# Sheet1.net
KiCad netlist of a schematic drawn in Altium Designer
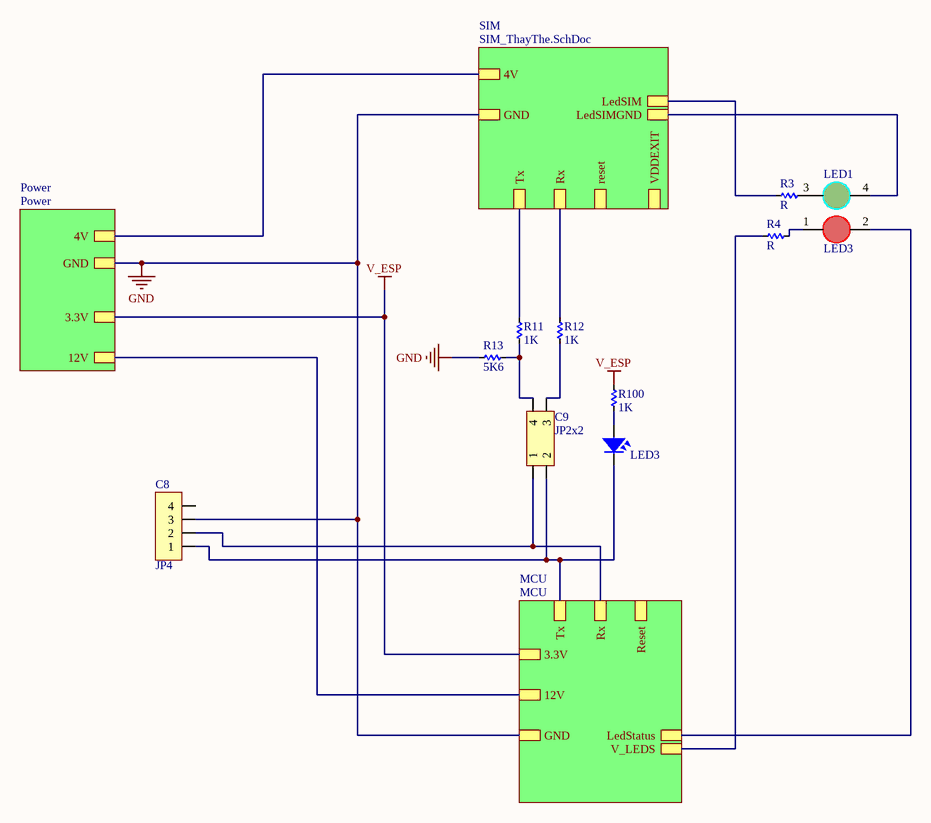
[diagram p0: Sheet1.SchDoc]

(export (version "E")
  (design (tool "Eeschema 10.0.6"))
  (components
    (comp (ref "C8")
      (value "JP4")
      (footprint "JP4-C1T")
      (description "WR-PHD 2.54 mm Angled Socket Header")
      (fields
        (field (name "MANUFACTURER") "Würth Elektronik eiSos GmbH")
        (field (name "PARTNO") "613004143121")
        (field (name "CREATED BY") "Karrer Zheng")
      )
      (libsource (lib "LIBRARY") (part "JP4"))
    )
    (comp (ref "C9")
      (value "JP2x2")
      (footprint "JP2-D2T")
      (description "WR-PHD 2.54 mm Dual Socket Header")
      (fields
        (field (name "MANUFACTURER") "Würth Elektronik eiSos GmbH")
        (field (name "PARTNO") "61300421821")
        (field (name "CREATED BY") "Karrer Zheng")
      )
      (libsource (lib "LIBRARY") (part "JP2x2"))
    )
    (comp (ref "LED1")
      (value "LED3")
      (footprint "LedC")
      (description "LED 3mm")
      (libsource (lib "nhan") (part "LED"))
    )
    (comp (ref "LED3")
      (value "LED")
      (footprint "LED-3MM-GREEN")
      (description "LED Single colour Green and Red")
      (libsource (lib "BanLinhKien") (part "LED"))
    )
    (comp (ref "R3") (value "R") (footprint "RES-SMD-0603_BIG") (libsource (lib "nhan") (part "R")))
    (comp (ref "R4") (value "R") (footprint "RES-SMD-0603_BIG") (libsource (lib "nhan") (part "R")))
    (comp (ref "R11")
      (value "1K")
      (footprint "RES-SMD-0805")
      (description "Resistor")
      (fields
        (field (name "MANUFACTURER") "Generic Components")
        (field (name "PUBLISHER") "Altium Hobart Technology Centre")
      )
      (libsource (lib "LIBRARY") (part "Res-SMD"))
    )
    (comp (ref "R12")
      (value "1K")
      (footprint "RES-SMD-0805")
      (description "Resistor")
      (fields
        (field (name "MANUFACTURER") "Generic Components")
        (field (name "PUBLISHER") "Altium Hobart Technology Centre")
      )
      (libsource (lib "LIBRARY") (part "Res-SMD"))
    )
    (comp (ref "R13")
      (value "5K6")
      (footprint "RES-SMD-0805")
      (description "Resistor")
      (fields
        (field (name "MANUFACTURER") "Generic Components")
        (field (name "PUBLISHER") "Altium Hobart Technology Centre")
      )
      (libsource (lib "LIBRARY") (part "Res-SMD"))
    )
    (comp (ref "R100")
      (value "1K")
      (footprint "RES-SMD-0805")
      (description "Resistor")
      (fields
        (field (name "MANUFACTURER") "Generic Components")
        (field (name "PUBLISHER") "Altium Hobart Technology Centre")
      )
      (libsource (lib "LIBRARY") (part "Res-SMD"))
    )
  )
  (nets
    (net (code "3") (name "/LedSIM") (class "Default")
      (node (ref "R3") (pin "2") (pinfunction "2_2") (pintype "passive"))
    )
    (net (code "4") (name "/LedSIMGND") (class "Default")
      (node (ref "LED1") (pin "4") (pinfunction "K_4") (pintype "passive"))
    )
    (net (code "5") (name "/LedStatus") (class "Default")
      (node (ref "LED1") (pin "2") (pinfunction "K_2") (pintype "passive"))
    )
    (net (code "7") (name "/Rx") (class "Default")
      (node (ref "R12") (pin "1") (pinfunction "1_1") (pintype "passive"))
    )
    (net (code "8") (name "/Rx_1") (class "Default")
      (node (ref "C8") (pin "2") (pinfunction "2_2") (pintype "passive"))
      (node (ref "C9") (pin "1") (pinfunction "1_1") (pintype "passive"))
    )
    (net (code "9") (name "/Tx") (class "Default")
      (node (ref "R11") (pin "1") (pinfunction "1_1") (pintype "passive"))
    )
    (net (code "10") (name "/Tx_1") (class "Default")
      (node (ref "C8") (pin "1") (pinfunction "1_1") (pintype "passive"))
      (node (ref "C9") (pin "2") (pinfunction "2_2") (pintype "passive"))
      (node (ref "LED3") (pin "2") (pinfunction "2_2") (pintype "passive"))
    )
    (net (code "12") (name "/V_LEDS") (class "Default")
      (node (ref "R4") (pin "2") (pinfunction "2_2") (pintype "passive"))
    )
    (net (code "14") (name "GND") (class "Default")
      (node (ref "C8") (pin "3") (pinfunction "3_3") (pintype "passive"))
      (node (ref "R13") (pin "2") (pinfunction "2_2") (pintype "passive"))
    )
    (net (code "15") (name "Net-(C9-Pad3)") (class "Default")
      (node (ref "C9") (pin "3") (pinfunction "3_3") (pintype "passive"))
      (node (ref "R12") (pin "2") (pinfunction "2_2") (pintype "passive"))
    )
    (net (code "16") (name "Net-(C9-Pad4)") (class "Default")
      (node (ref "C9") (pin "4") (pinfunction "4_4") (pintype "passive"))
      (node (ref "R11") (pin "2") (pinfunction "2_2") (pintype "passive"))
      (node (ref "R13") (pin "1") (pinfunction "1_1") (pintype "passive"))
    )
    (net (code "17") (name "Net-(LED1-A-Pad1)") (class "Default")
      (node (ref "LED1") (pin "1") (pinfunction "A_1") (pintype "passive"))
      (node (ref "R4") (pin "1") (pinfunction "1_1") (pintype "passive"))
    )
    (net (code "18") (name "Net-(LED1-A-Pad3)") (class "Default")
      (node (ref "LED1") (pin "3") (pinfunction "A_3") (pintype "passive"))
      (node (ref "R3") (pin "1") (pinfunction "1_1") (pintype "passive"))
    )
    (net (code "19") (name "Net-(LED3-Pad1)") (class "Default")
      (node (ref "LED3") (pin "1") (pinfunction "1_1") (pintype "passive"))
      (node (ref "R100") (pin "1") (pinfunction "1_1") (pintype "passive"))
    )
    (net (code "20") (name "V_ESP") (class "Default")
      (node (ref "R100") (pin "2") (pinfunction "2_2") (pintype "passive"))
    )
    (net (code "21") (name "unconnected-(C8-Pad4)") (class "Default")
      (node (ref "C8") (pin "4") (pinfunction "4_4") (pintype "passive"))
    )
  )
)
